# zigtherm.net
KiCad netlist of a schematic drawn in EAGLE
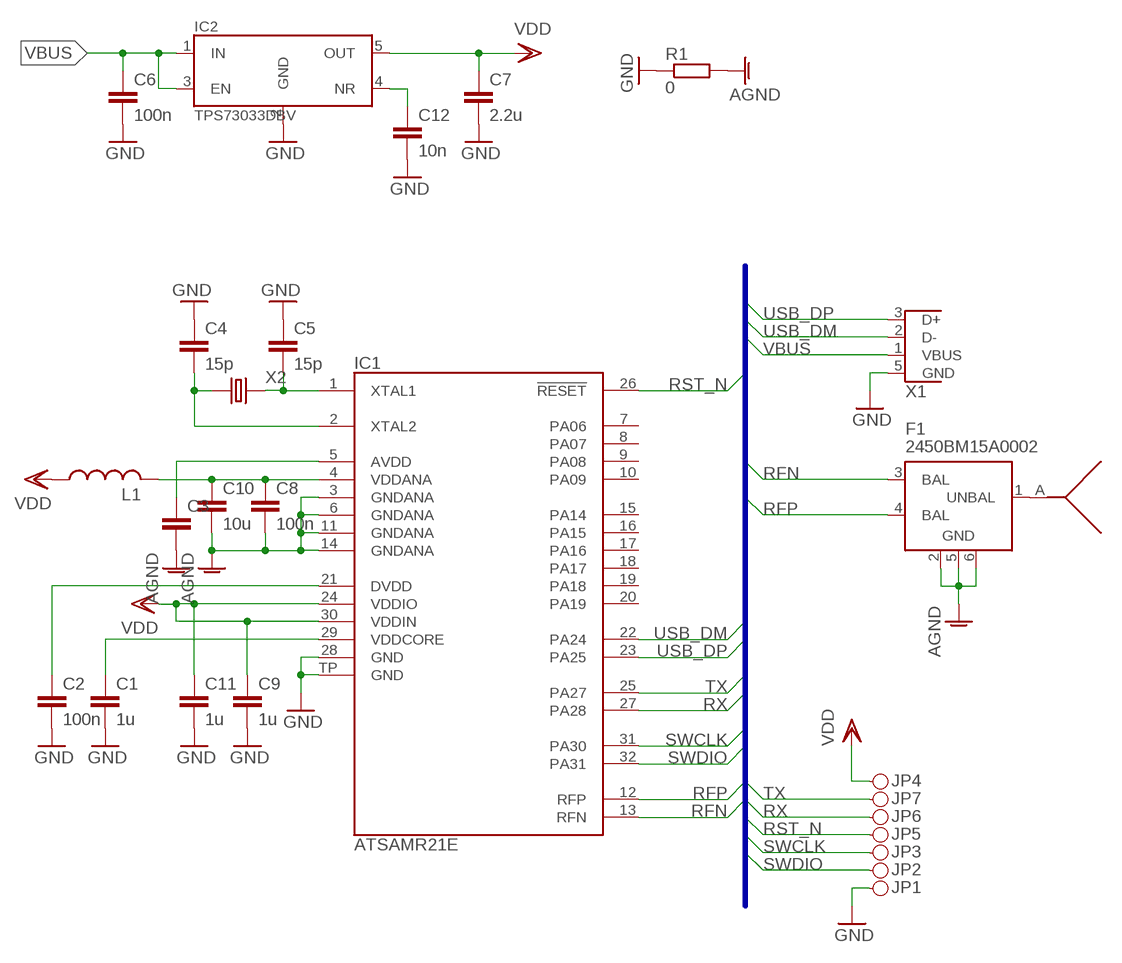
[diagram p0: schematic, sheet 1]

(export (version "E")
  (design (tool "Eeschema 10.0.6"))
  (components
    (comp (ref "AE1")
      (value "INVERTED_F_ANTENNA")
      (footprint "eagle-import:INVERTED_F_ANTENNA")
      (libsource (lib "eagle-import") (part "INVERTED_F_ANTENNA"))
    )
    (comp (ref "C1")
      (value "1u")
      (footprint "eagle-import:C0603")
      (libsource (lib "eagle-import") (part "C-EUC0603"))
    )
    (comp (ref "C2")
      (value "100n")
      (footprint "eagle-import:C0603")
      (libsource (lib "eagle-import") (part "C-EUC0603"))
    )
    (comp (ref "C3")
      (value "C-EUC0603")
      (footprint "eagle-import:C0603")
      (libsource (lib "eagle-import") (part "C-EUC0603"))
    )
    (comp (ref "C4")
      (value "15p")
      (footprint "eagle-import:C0603")
      (libsource (lib "eagle-import") (part "C-EUC0603"))
    )
    (comp (ref "C5")
      (value "15p")
      (footprint "eagle-import:C0603")
      (libsource (lib "eagle-import") (part "C-EUC0603"))
    )
    (comp (ref "C6")
      (value "100n")
      (footprint "eagle-import:C0603")
      (libsource (lib "eagle-import") (part "C-EUC0603"))
    )
    (comp (ref "C7")
      (value "2.2u")
      (footprint "eagle-import:C0603")
      (libsource (lib "eagle-import") (part "C-EUC0603"))
    )
    (comp (ref "C8")
      (value "100n")
      (footprint "eagle-import:C0603")
      (libsource (lib "eagle-import") (part "C-EUC0603"))
    )
    (comp (ref "C9")
      (value "1u")
      (footprint "eagle-import:C0603")
      (libsource (lib "eagle-import") (part "C-EUC0603"))
    )
    (comp (ref "C10")
      (value "10u")
      (footprint "eagle-import:C0603")
      (libsource (lib "eagle-import") (part "C-EUC0603"))
    )
    (comp (ref "C11")
      (value "1u")
      (footprint "eagle-import:C0603")
      (libsource (lib "eagle-import") (part "C-EUC0603"))
    )
    (comp (ref "C12")
      (value "10n")
      (footprint "eagle-import:C0603")
      (libsource (lib "eagle-import") (part "C-EUC0603"))
    )
    (comp (ref "F1")
      (value "2450BM15A0002")
      (footprint "eagle-import:2450BM15A0002")
      (libsource (lib "eagle-import") (part "2450BM15A0002"))
    )
    (comp (ref "IC1")
      (value "ATSAMR21E")
      (footprint "eagle-import:QFN32")
      (libsource (lib "eagle-import") (part "ATSAMR21E"))
    )
    (comp (ref "IC2")
      (value "TPS73033DBV")
      (footprint "eagle-import:SOT23-DBV")
      (libsource (lib "eagle-import") (part "TPS73033DBV"))
    )
    (comp (ref "JP1")
      (value "PINH1X01SMD")
      (footprint "eagle-import:PINH1X01SMD")
      (libsource (lib "eagle-import") (part "PINH1X01SMD"))
    )
    (comp (ref "JP2")
      (value "PINH1X01SMD")
      (footprint "eagle-import:PINH1X01SMD")
      (libsource (lib "eagle-import") (part "PINH1X01SMD"))
    )
    (comp (ref "JP3")
      (value "PINH1X01SMD")
      (footprint "eagle-import:PINH1X01SMD")
      (libsource (lib "eagle-import") (part "PINH1X01SMD"))
    )
    (comp (ref "JP4")
      (value "PINH1X01SMD")
      (footprint "eagle-import:PINH1X01SMD")
      (libsource (lib "eagle-import") (part "PINH1X01SMD"))
    )
    (comp (ref "JP5")
      (value "PINH1X01SMD")
      (footprint "eagle-import:PINH1X01SMD")
      (libsource (lib "eagle-import") (part "PINH1X01SMD"))
    )
    (comp (ref "JP6")
      (value "PINH1X01SMD")
      (footprint "eagle-import:PINH1X01SMD")
      (libsource (lib "eagle-import") (part "PINH1X01SMD"))
    )
    (comp (ref "JP7")
      (value "PINH1X01SMD")
      (footprint "eagle-import:PINH1X01SMD")
      (libsource (lib "eagle-import") (part "PINH1X01SMD"))
    )
    (comp (ref "L1")
      (value "L-USL2012C")
      (footprint "eagle-import:L2012C")
      (libsource (lib "eagle-import") (part "L-USL2012C"))
    )
    (comp (ref "R1")
      (value "0")
      (footprint "eagle-import:R0603")
      (libsource (lib "eagle-import") (part "R-EU_R0603"))
    )
    (comp (ref "X1")
      (value "USB-MICRO-B-BOTTOM-MOLEX")
      (footprint "eagle-import:USB-MICRO-B-BOTTOM-MOLEX")
      (libsource (lib "eagle-import") (part "USB-MICRO-B-BOTTOM-MOLEX"))
    )
    (comp (ref "X2")
      (value "XTAL3.2X2.5")
      (footprint "eagle-import:3.2X2.5")
      (libsource (lib "eagle-import") (part "XTAL3.2X2.5"))
    )
  )
  (nets
    (net (code "1") (name "/RFN") (class "Default")
      (node (ref "F1") (pin "3") (pinfunction "BAL_3") (pintype "passive"))
      (node (ref "IC1") (pin "13") (pinfunction "RFN_13") (pintype "passive"))
    )
    (net (code "2") (name "/RFP") (class "Default")
      (node (ref "F1") (pin "4") (pinfunction "BAL_4") (pintype "passive"))
      (node (ref "IC1") (pin "12") (pinfunction "RFP_12") (pintype "passive"))
    )
    (net (code "3") (name "/RST_N") (class "Default")
      (node (ref "IC1") (pin "26") (pinfunction "~{RESET}_26") (pintype "input"))
      (node (ref "JP5") (pin "1") (pinfunction "1_1") (pintype "passive"))
    )
    (net (code "4") (name "/RX") (class "Default")
      (node (ref "IC1") (pin "27") (pinfunction "PA28_27") (pintype "bidirectional"))
      (node (ref "JP6") (pin "1") (pinfunction "1_1") (pintype "passive"))
    )
    (net (code "5") (name "/SWCLK") (class "Default")
      (node (ref "IC1") (pin "31") (pinfunction "PA30_31") (pintype "bidirectional"))
      (node (ref "JP3") (pin "1") (pinfunction "1_1") (pintype "passive"))
    )
    (net (code "6") (name "/SWDIO") (class "Default")
      (node (ref "IC1") (pin "32") (pinfunction "PA31_32") (pintype "bidirectional"))
      (node (ref "JP2") (pin "1") (pinfunction "1_1") (pintype "passive"))
    )
    (net (code "7") (name "/TX") (class "Default")
      (node (ref "IC1") (pin "25") (pinfunction "PA27_25") (pintype "bidirectional"))
      (node (ref "JP7") (pin "1") (pinfunction "1_1") (pintype "passive"))
    )
    (net (code "8") (name "/USB_DM") (class "Default")
      (node (ref "IC1") (pin "22") (pinfunction "PA24_22") (pintype "bidirectional"))
      (node (ref "X1") (pin "2") (pinfunction "D-_2") (pintype "bidirectional"))
    )
    (net (code "9") (name "/USB_DP") (class "Default")
      (node (ref "IC1") (pin "23") (pinfunction "PA25_23") (pintype "bidirectional"))
      (node (ref "X1") (pin "3") (pinfunction "D+_3") (pintype "bidirectional"))
    )
    (net (code "10") (name "AGND") (class "Default")
      (node (ref "C10") (pin "2") (pinfunction "2_2") (pintype "passive"))
      (node (ref "C3") (pin "2") (pinfunction "2_2") (pintype "passive"))
      (node (ref "C8") (pin "2") (pinfunction "2_2") (pintype "passive"))
      (node (ref "F1") (pin "2") (pinfunction "GND_2") (pintype "passive"))
      (node (ref "F1") (pin "5") (pinfunction "GND_5") (pintype "passive"))
      (node (ref "F1") (pin "6") (pinfunction "GND_6") (pintype "passive"))
      (node (ref "IC1") (pin "11") (pinfunction "GNDANA_11") (pintype "passive"))
      (node (ref "IC1") (pin "14") (pinfunction "GNDANA_14") (pintype "passive"))
      (node (ref "IC1") (pin "3") (pinfunction "GNDANA_3") (pintype "passive"))
      (node (ref "IC1") (pin "6") (pinfunction "GNDANA_6") (pintype "passive"))
      (node (ref "R1") (pin "2") (pinfunction "2_2") (pintype "passive"))
    )
    (net (code "11") (name "GND") (class "Default")
      (node (ref "C1") (pin "2") (pinfunction "2_2") (pintype "passive"))
      (node (ref "C11") (pin "2") (pinfunction "2_2") (pintype "passive"))
      (node (ref "C12") (pin "2") (pinfunction "2_2") (pintype "passive"))
      (node (ref "C2") (pin "2") (pinfunction "2_2") (pintype "passive"))
      (node (ref "C4") (pin "1") (pinfunction "1_1") (pintype "passive"))
      (node (ref "C5") (pin "1") (pinfunction "1_1") (pintype "passive"))
      (node (ref "C6") (pin "2") (pinfunction "2_2") (pintype "passive"))
      (node (ref "C7") (pin "2") (pinfunction "2_2") (pintype "passive"))
      (node (ref "C9") (pin "2") (pinfunction "2_2") (pintype "passive"))
      (node (ref "IC1") (pin "28") (pinfunction "GND_28") (pintype "passive"))
      (node (ref "IC1") (pin "TP") (pinfunction "GND_TP") (pintype "passive"))
      (node (ref "IC2") (pin "2") (pinfunction "GND_2") (pintype "passive"))
      (node (ref "JP1") (pin "1") (pinfunction "1_1") (pintype "passive"))
      (node (ref "R1") (pin "1") (pinfunction "1_1") (pintype "passive"))
      (node (ref "X1") (pin "5") (pinfunction "GND_5") (pintype "passive"))
    )
    (net (code "12") (name "Net-(F1-UNBAL)") (class "Default")
      (node (ref "AE1") (pin "A") (pinfunction "A_A") (pintype "passive"))
      (node (ref "F1") (pin "1") (pinfunction "UNBAL_1") (pintype "passive"))
    )
    (net (code "13") (name "Net-(IC1-AVDD)") (class "Default")
      (node (ref "C3") (pin "1") (pinfunction "1_1") (pintype "passive"))
      (node (ref "IC1") (pin "5") (pinfunction "AVDD_5") (pintype "passive"))
    )
    (net (code "14") (name "Net-(IC1-DVDD)") (class "Default")
      (node (ref "C2") (pin "1") (pinfunction "1_1") (pintype "passive"))
      (node (ref "IC1") (pin "21") (pinfunction "DVDD_21") (pintype "passive"))
    )
    (net (code "15") (name "Net-(IC1-VDDANA)") (class "Default")
      (node (ref "C10") (pin "1") (pinfunction "1_1") (pintype "passive"))
      (node (ref "C8") (pin "1") (pinfunction "1_1") (pintype "passive"))
      (node (ref "IC1") (pin "4") (pinfunction "VDDANA_4") (pintype "passive"))
      (node (ref "L1") (pin "2") (pinfunction "2_2") (pintype "passive"))
    )
    (net (code "16") (name "Net-(IC1-VDDCORE)") (class "Default")
      (node (ref "C1") (pin "1") (pinfunction "1_1") (pintype "passive"))
      (node (ref "IC1") (pin "29") (pinfunction "VDDCORE_29") (pintype "passive"))
    )
    (net (code "17") (name "Net-(IC1-XTAL1)") (class "Default")
      (node (ref "C5") (pin "2") (pinfunction "2_2") (pintype "passive"))
      (node (ref "IC1") (pin "1") (pinfunction "XTAL1_1") (pintype "passive"))
      (node (ref "X2") (pin "3") (pinfunction "2_3") (pintype "passive"))
    )
    (net (code "18") (name "Net-(IC1-XTAL2)") (class "Default")
      (node (ref "C4") (pin "2") (pinfunction "2_2") (pintype "passive"))
      (node (ref "IC1") (pin "2") (pinfunction "XTAL2_2") (pintype "passive"))
      (node (ref "X2") (pin "1") (pinfunction "1_1") (pintype "passive"))
    )
    (net (code "19") (name "Net-(IC2-NR)") (class "Default")
      (node (ref "C12") (pin "1") (pinfunction "1_1") (pintype "passive"))
      (node (ref "IC2") (pin "4") (pinfunction "NR_4") (pintype "passive"))
    )
    (net (code "20") (name "VBUS") (class "Default")
      (node (ref "C6") (pin "1") (pinfunction "1_1") (pintype "passive"))
      (node (ref "IC2") (pin "1") (pinfunction "IN_1") (pintype "passive"))
      (node (ref "IC2") (pin "3") (pinfunction "EN_3") (pintype "input"))
      (node (ref "X1") (pin "1") (pinfunction "VBUS_1") (pintype "passive"))
    )
    (net (code "21") (name "VDD") (class "Default")
      (node (ref "C11") (pin "1") (pinfunction "1_1") (pintype "passive"))
      (node (ref "C7") (pin "1") (pinfunction "1_1") (pintype "passive"))
      (node (ref "C9") (pin "1") (pinfunction "1_1") (pintype "passive"))
      (node (ref "IC1") (pin "24") (pinfunction "VDDIO_24") (pintype "passive"))
      (node (ref "IC1") (pin "30") (pinfunction "VDDIN_30") (pintype "passive"))
      (node (ref "IC2") (pin "5") (pinfunction "OUT_5") (pintype "passive"))
      (node (ref "JP4") (pin "1") (pinfunction "1_1") (pintype "passive"))
      (node (ref "L1") (pin "1") (pinfunction "1_1") (pintype "passive"))
    )
    (net (code "22") (name "unconnected-(IC1-PA06-Pad7)") (class "Default")
      (node (ref "IC1") (pin "7") (pinfunction "PA06_7") (pintype "bidirectional"))
    )
    (net (code "23") (name "unconnected-(IC1-PA07-Pad8)") (class "Default")
      (node (ref "IC1") (pin "8") (pinfunction "PA07_8") (pintype "bidirectional"))
    )
    (net (code "24") (name "unconnected-(IC1-PA08-Pad9)") (class "Default")
      (node (ref "IC1") (pin "9") (pinfunction "PA08_9") (pintype "bidirectional"))
    )
    (net (code "25") (name "unconnected-(IC1-PA09-Pad10)") (class "Default")
      (node (ref "IC1") (pin "10") (pinfunction "PA09_10") (pintype "bidirectional"))
    )
    (net (code "26") (name "unconnected-(IC1-PA14-Pad15)") (class "Default")
      (node (ref "IC1") (pin "15") (pinfunction "PA14_15") (pintype "bidirectional"))
    )
    (net (code "27") (name "unconnected-(IC1-PA15-Pad16)") (class "Default")
      (node (ref "IC1") (pin "16") (pinfunction "PA15_16") (pintype "bidirectional"))
    )
    (net (code "28") (name "unconnected-(IC1-PA16-Pad17)") (class "Default")
      (node (ref "IC1") (pin "17") (pinfunction "PA16_17") (pintype "bidirectional"))
    )
    (net (code "29") (name "unconnected-(IC1-PA17-Pad18)") (class "Default")
      (node (ref "IC1") (pin "18") (pinfunction "PA17_18") (pintype "bidirectional"))
    )
    (net (code "30") (name "unconnected-(IC1-PA18-Pad19)") (class "Default")
      (node (ref "IC1") (pin "19") (pinfunction "PA18_19") (pintype "bidirectional"))
    )
    (net (code "31") (name "unconnected-(IC1-PA19-Pad20)") (class "Default")
      (node (ref "IC1") (pin "20") (pinfunction "PA19_20") (pintype "bidirectional"))
    )
  )
)
